# HV_Side.net
KiCad netlist of a schematic drawn in Altium Designer
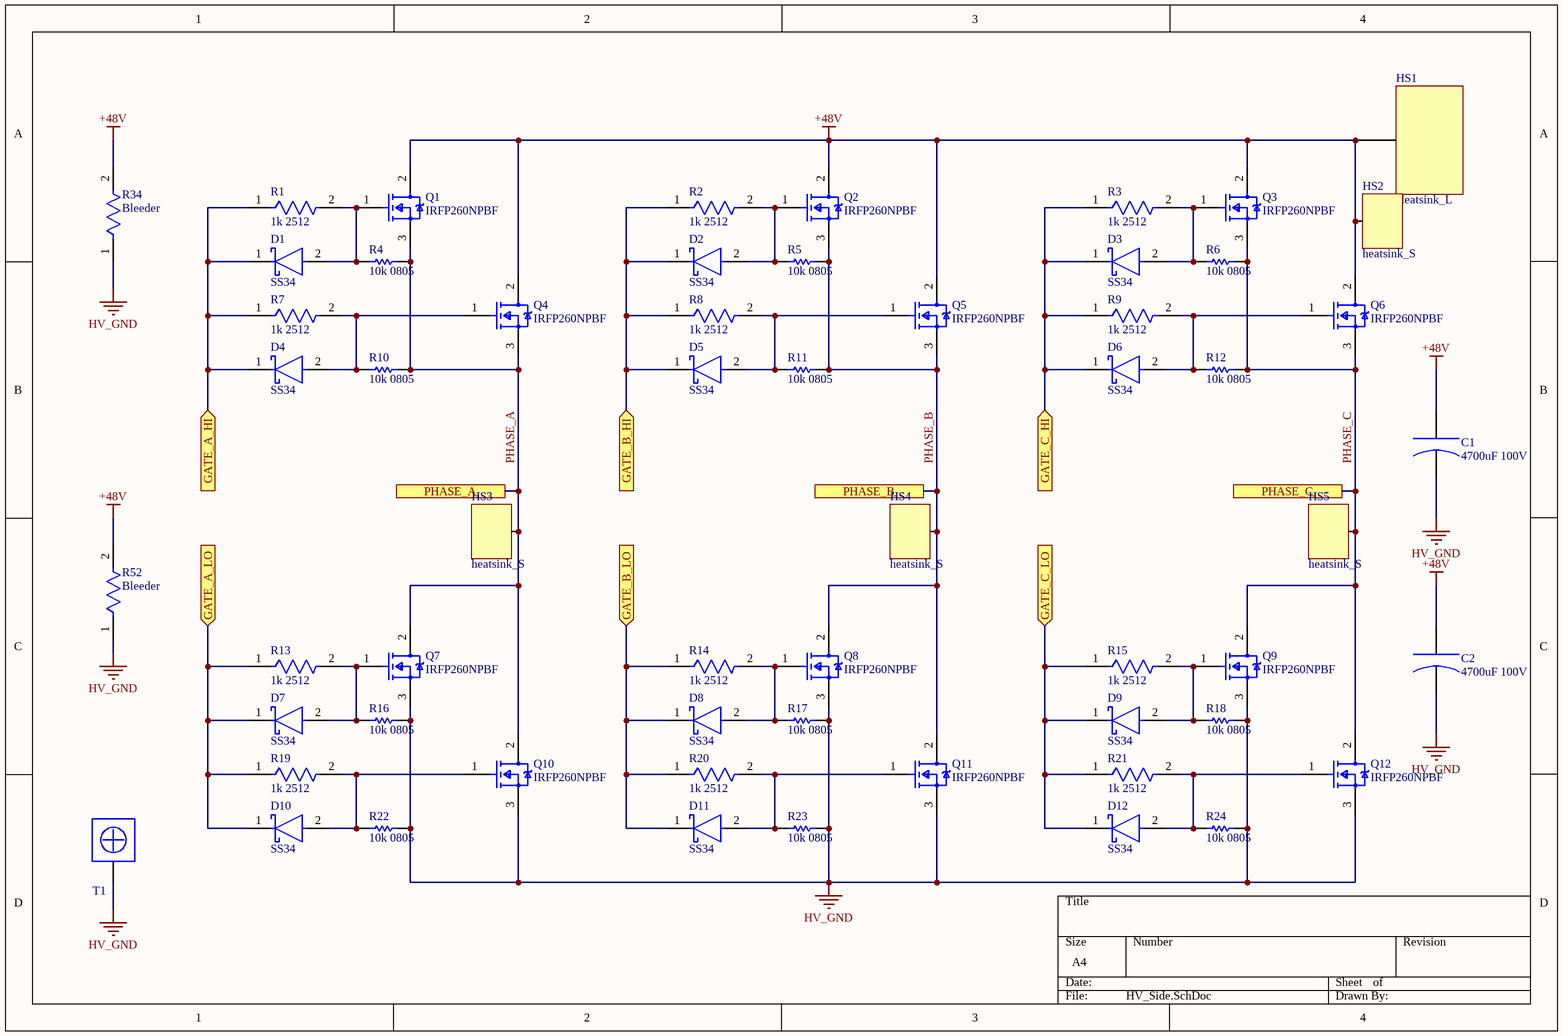
[diagram p0: HV_Side.SchDoc]

(export (version "E")
  (design (tool "Eeschema 10.0.6"))
  (components
    (comp (ref "C1")
      (value "4700uF 100V")
      (footprint "4700uF 100V")
      (description "4700uF 100V Electrolytic Capacitor")
      (libsource (lib "1kW_BLDC_Controller") (part "4700uF 100V"))
    )
    (comp (ref "C2")
      (value "4700uF 100V")
      (footprint "4700uF 100V")
      (description "4700uF 100V Electrolytic Capacitor")
      (libsource (lib "1kW_BLDC_Controller") (part "4700uF 100V"))
    )
    (comp (ref "D1")
      (value "SS34")
      (footprint "DO-214AC")
      (description "SS34 SMA 40V/3A Schottky Diode SMD Package-DO-214AC")
      (fields
        (field (name "MANUFACTURER") "Vishay Semiconductors")
        (field (name "MANUFACTURER PART NUMBER") "SS34-E3/57T")
      )
      (libsource (lib "1kW_BLDC_Controller") (part "SS34"))
    )
    (comp (ref "D2")
      (value "SS34")
      (footprint "DO-214AC")
      (description "SS34 SMA 40V/3A Schottky Diode SMD Package-DO-214AC")
      (fields
        (field (name "MANUFACTURER") "Vishay Semiconductors")
        (field (name "MANUFACTURER PART NUMBER") "SS34-E3/57T")
      )
      (libsource (lib "1kW_BLDC_Controller") (part "SS34"))
    )
    (comp (ref "D3")
      (value "SS34")
      (footprint "DO-214AC")
      (description "SS34 SMA 40V/3A Schottky Diode SMD Package-DO-214AC")
      (fields
        (field (name "MANUFACTURER") "Vishay Semiconductors")
        (field (name "MANUFACTURER PART NUMBER") "SS34-E3/57T")
      )
      (libsource (lib "1kW_BLDC_Controller") (part "SS34"))
    )
    (comp (ref "D4")
      (value "SS34")
      (footprint "DO-214AC")
      (description "SS34 SMA 40V/3A Schottky Diode SMD Package-DO-214AC")
      (fields
        (field (name "MANUFACTURER") "Vishay Semiconductors")
        (field (name "MANUFACTURER PART NUMBER") "SS34-E3/57T")
      )
      (libsource (lib "1kW_BLDC_Controller") (part "SS34"))
    )
    (comp (ref "D5")
      (value "SS34")
      (footprint "DO-214AC")
      (description "SS34 SMA 40V/3A Schottky Diode SMD Package-DO-214AC")
      (fields
        (field (name "MANUFACTURER") "Vishay Semiconductors")
        (field (name "MANUFACTURER PART NUMBER") "SS34-E3/57T")
      )
      (libsource (lib "1kW_BLDC_Controller") (part "SS34"))
    )
    (comp (ref "D6")
      (value "SS34")
      (footprint "DO-214AC")
      (description "SS34 SMA 40V/3A Schottky Diode SMD Package-DO-214AC")
      (fields
        (field (name "MANUFACTURER") "Vishay Semiconductors")
        (field (name "MANUFACTURER PART NUMBER") "SS34-E3/57T")
      )
      (libsource (lib "1kW_BLDC_Controller") (part "SS34"))
    )
    (comp (ref "D7")
      (value "SS34")
      (footprint "DO-214AC")
      (description "SS34 SMA 40V/3A Schottky Diode SMD Package-DO-214AC")
      (fields
        (field (name "MANUFACTURER") "Vishay Semiconductors")
        (field (name "MANUFACTURER PART NUMBER") "SS34-E3/57T")
      )
      (libsource (lib "1kW_BLDC_Controller") (part "SS34"))
    )
    (comp (ref "D8")
      (value "SS34")
      (footprint "DO-214AC")
      (description "SS34 SMA 40V/3A Schottky Diode SMD Package-DO-214AC")
      (fields
        (field (name "MANUFACTURER") "Vishay Semiconductors")
        (field (name "MANUFACTURER PART NUMBER") "SS34-E3/57T")
      )
      (libsource (lib "1kW_BLDC_Controller") (part "SS34"))
    )
    (comp (ref "D9")
      (value "SS34")
      (footprint "DO-214AC")
      (description "SS34 SMA 40V/3A Schottky Diode SMD Package-DO-214AC")
      (fields
        (field (name "MANUFACTURER") "Vishay Semiconductors")
        (field (name "MANUFACTURER PART NUMBER") "SS34-E3/57T")
      )
      (libsource (lib "1kW_BLDC_Controller") (part "SS34"))
    )
    (comp (ref "D10")
      (value "SS34")
      (footprint "DO-214AC")
      (description "SS34 SMA 40V/3A Schottky Diode SMD Package-DO-214AC")
      (fields
        (field (name "MANUFACTURER") "Vishay Semiconductors")
        (field (name "MANUFACTURER PART NUMBER") "SS34-E3/57T")
      )
      (libsource (lib "1kW_BLDC_Controller") (part "SS34"))
    )
    (comp (ref "D11")
      (value "SS34")
      (footprint "DO-214AC")
      (description "SS34 SMA 40V/3A Schottky Diode SMD Package-DO-214AC")
      (fields
        (field (name "MANUFACTURER") "Vishay Semiconductors")
        (field (name "MANUFACTURER PART NUMBER") "SS34-E3/57T")
      )
      (libsource (lib "1kW_BLDC_Controller") (part "SS34"))
    )
    (comp (ref "D12")
      (value "SS34")
      (footprint "DO-214AC")
      (description "SS34 SMA 40V/3A Schottky Diode SMD Package-DO-214AC")
      (fields
        (field (name "MANUFACTURER") "Vishay Semiconductors")
        (field (name "MANUFACTURER PART NUMBER") "SS34-E3/57T")
      )
      (libsource (lib "1kW_BLDC_Controller") (part "SS34"))
    )
    (comp (ref "HS1")
      (value "Heatsink_L")
      (footprint "heatsink_l")
      (libsource (lib "1kW_BLDC_Controller") (part "Heatsink_L"))
    )
    (comp (ref "HS2")
      (value "heatsink_S")
      (footprint "haetsink_s")
      (libsource (lib "") (part "heatsink_S_1"))
    )
    (comp (ref "HS3")
      (value "heatsink_S")
      (footprint "haetsink_s")
      (libsource (lib "1kW_BLDC_Controller") (part "heatsink_S"))
    )
    (comp (ref "HS4")
      (value "heatsink_S")
      (footprint "haetsink_s")
      (libsource (lib "1kW_BLDC_Controller") (part "heatsink_S"))
    )
    (comp (ref "HS5")
      (value "heatsink_S")
      (footprint "haetsink_s")
      (libsource (lib "1kW_BLDC_Controller") (part "heatsink_S"))
    )
    (comp (ref "Q1")
      (value "IRFP260NPBF")
      (footprint "FP-PG-TO247-3-MFG")
      (description "MOSFET N-CH 200V 50A TO247AC")
      (libsource (lib "Altium Content Vault") (part "b09f7f152735e370c1ea22a33fa83d6"))
    )
    (comp (ref "Q2")
      (value "IRFP260NPBF")
      (footprint "FP-PG-TO247-3-MFG")
      (description "MOSFET N-CH 200V 50A TO247AC")
      (libsource (lib "Altium Content Vault") (part "b09f7f152735e370c1ea22a33fa83d6"))
    )
    (comp (ref "Q3")
      (value "IRFP260NPBF")
      (footprint "FP-PG-TO247-3-MFG")
      (description "MOSFET N-CH 200V 50A TO247AC")
      (libsource (lib "Altium Content Vault") (part "b09f7f152735e370c1ea22a33fa83d6"))
    )
    (comp (ref "Q4")
      (value "IRFP260NPBF")
      (footprint "FP-PG-TO247-3-MFG")
      (description "MOSFET N-CH 200V 50A TO247AC")
      (libsource (lib "Altium Content Vault") (part "b09f7f152735e370c1ea22a33fa83d6"))
    )
    (comp (ref "Q5")
      (value "IRFP260NPBF")
      (footprint "FP-PG-TO247-3-MFG")
      (description "MOSFET N-CH 200V 50A TO247AC")
      (libsource (lib "Altium Content Vault") (part "b09f7f152735e370c1ea22a33fa83d6"))
    )
    (comp (ref "Q6")
      (value "IRFP260NPBF")
      (footprint "FP-PG-TO247-3-MFG")
      (description "MOSFET N-CH 200V 50A TO247AC")
      (libsource (lib "Altium Content Vault") (part "b09f7f152735e370c1ea22a33fa83d6"))
    )
    (comp (ref "Q7")
      (value "IRFP260NPBF")
      (footprint "FP-PG-TO247-3-MFG")
      (description "MOSFET N-CH 200V 50A TO247AC")
      (libsource (lib "Altium Content Vault") (part "b09f7f152735e370c1ea22a33fa83d6"))
    )
    (comp (ref "Q8")
      (value "IRFP260NPBF")
      (footprint "FP-PG-TO247-3-MFG")
      (description "MOSFET N-CH 200V 50A TO247AC")
      (libsource (lib "Altium Content Vault") (part "b09f7f152735e370c1ea22a33fa83d6"))
    )
    (comp (ref "Q9")
      (value "IRFP260NPBF")
      (footprint "FP-PG-TO247-3-MFG")
      (description "MOSFET N-CH 200V 50A TO247AC")
      (libsource (lib "Altium Content Vault") (part "b09f7f152735e370c1ea22a33fa83d6"))
    )
    (comp (ref "Q10")
      (value "IRFP260NPBF")
      (footprint "FP-PG-TO247-3-MFG")
      (description "MOSFET N-CH 200V 50A TO247AC")
      (libsource (lib "Altium Content Vault") (part "b09f7f152735e370c1ea22a33fa83d6"))
    )
    (comp (ref "Q11")
      (value "IRFP260NPBF")
      (footprint "FP-PG-TO247-3-MFG")
      (description "MOSFET N-CH 200V 50A TO247AC")
      (libsource (lib "Altium Content Vault") (part "b09f7f152735e370c1ea22a33fa83d6"))
    )
    (comp (ref "Q12")
      (value "IRFP260NPBF")
      (footprint "FP-PG-TO247-3-MFG")
      (description "MOSFET N-CH 200V 50A TO247AC")
      (libsource (lib "Altium Content Vault") (part "b09f7f152735e370c1ea22a33fa83d6"))
    )
    (comp (ref "R1")
      (value "1k 2512")
      (footprint "R2512")
      (description "1K Ohm 1W Resistor 2512 Package")
      (fields (field (name "TOLERANCE") "1%") (field (name "MANUFACTURER") "Vishay Dale"))
      (libsource (lib "1kW_BLDC_Controller") (part "1K_2512"))
    )
    (comp (ref "R2")
      (value "1k 2512")
      (footprint "R2512")
      (description "1K Ohm 1W Resistor 2512 Package")
      (fields (field (name "TOLERANCE") "1%") (field (name "MANUFACTURER") "Vishay Dale"))
      (libsource (lib "1kW_BLDC_Controller") (part "1K_2512"))
    )
    (comp (ref "R3")
      (value "1k 2512")
      (footprint "R2512")
      (description "1K Ohm 1W Resistor 2512 Package")
      (fields (field (name "TOLERANCE") "1%") (field (name "MANUFACTURER") "Vishay Dale"))
      (libsource (lib "1kW_BLDC_Controller") (part "1K_2512"))
    )
    (comp (ref "R4")
      (value "10k 0805")
      (footprint "R0805")
      (description "10K Ohm 1/8 Watt Resistor 1% Tolerance RC0805FR-0710KL – 0805 Package")
      (libsource (lib "1kW_BLDC_Controller") (part "10k 0805"))
    )
    (comp (ref "R5")
      (value "10k 0805")
      (footprint "R0805")
      (description "10K Ohm 1/8 Watt Resistor 1% Tolerance RC0805FR-0710KL – 0805 Package")
      (libsource (lib "1kW_BLDC_Controller") (part "10k 0805"))
    )
    (comp (ref "R6")
      (value "10k 0805")
      (footprint "R0805")
      (description "10K Ohm 1/8 Watt Resistor 1% Tolerance RC0805FR-0710KL – 0805 Package")
      (libsource (lib "1kW_BLDC_Controller") (part "10k 0805"))
    )
    (comp (ref "R7")
      (value "1k 2512")
      (footprint "R2512")
      (description "1K Ohm 1W Resistor 2512 Package")
      (fields (field (name "TOLERANCE") "1%") (field (name "MANUFACTURER") "Vishay Dale"))
      (libsource (lib "1kW_BLDC_Controller") (part "1K_2512"))
    )
    (comp (ref "R8")
      (value "1k 2512")
      (footprint "R2512")
      (description "1K Ohm 1W Resistor 2512 Package")
      (fields (field (name "TOLERANCE") "1%") (field (name "MANUFACTURER") "Vishay Dale"))
      (libsource (lib "1kW_BLDC_Controller") (part "1K_2512"))
    )
    (comp (ref "R9")
      (value "1k 2512")
      (footprint "R2512")
      (description "1K Ohm 1W Resistor 2512 Package")
      (fields (field (name "TOLERANCE") "1%") (field (name "MANUFACTURER") "Vishay Dale"))
      (libsource (lib "1kW_BLDC_Controller") (part "1K_2512"))
    )
    (comp (ref "R10")
      (value "10k 0805")
      (footprint "R0805")
      (description "10K Ohm 1/8 Watt Resistor 1% Tolerance RC0805FR-0710KL – 0805 Package")
      (libsource (lib "1kW_BLDC_Controller") (part "10k 0805"))
    )
    (comp (ref "R11")
      (value "10k 0805")
      (footprint "R0805")
      (description "10K Ohm 1/8 Watt Resistor 1% Tolerance RC0805FR-0710KL – 0805 Package")
      (libsource (lib "1kW_BLDC_Controller") (part "10k 0805"))
    )
    (comp (ref "R12")
      (value "10k 0805")
      (footprint "R0805")
      (description "10K Ohm 1/8 Watt Resistor 1% Tolerance RC0805FR-0710KL – 0805 Package")
      (libsource (lib "1kW_BLDC_Controller") (part "10k 0805"))
    )
    (comp (ref "R13")
      (value "1k 2512")
      (footprint "R2512")
      (description "1K Ohm 1W Resistor 2512 Package")
      (fields (field (name "TOLERANCE") "1%") (field (name "MANUFACTURER") "Vishay Dale"))
      (libsource (lib "1kW_BLDC_Controller") (part "1K_2512"))
    )
    (comp (ref "R14")
      (value "1k 2512")
      (footprint "R2512")
      (description "1K Ohm 1W Resistor 2512 Package")
      (fields (field (name "TOLERANCE") "1%") (field (name "MANUFACTURER") "Vishay Dale"))
      (libsource (lib "1kW_BLDC_Controller") (part "1K_2512"))
    )
    (comp (ref "R15")
      (value "1k 2512")
      (footprint "R2512")
      (description "1K Ohm 1W Resistor 2512 Package")
      (fields (field (name "TOLERANCE") "1%") (field (name "MANUFACTURER") "Vishay Dale"))
      (libsource (lib "1kW_BLDC_Controller") (part "1K_2512"))
    )
    (comp (ref "R16")
      (value "10k 0805")
      (footprint "R0805")
      (description "10K Ohm 1/8 Watt Resistor 1% Tolerance RC0805FR-0710KL – 0805 Package")
      (libsource (lib "1kW_BLDC_Controller") (part "10k 0805"))
    )
    (comp (ref "R17")
      (value "10k 0805")
      (footprint "R0805")
      (description "10K Ohm 1/8 Watt Resistor 1% Tolerance RC0805FR-0710KL – 0805 Package")
      (libsource (lib "1kW_BLDC_Controller") (part "10k 0805"))
    )
    (comp (ref "R18")
      (value "10k 0805")
      (footprint "R0805")
      (description "10K Ohm 1/8 Watt Resistor 1% Tolerance RC0805FR-0710KL – 0805 Package")
      (libsource (lib "1kW_BLDC_Controller") (part "10k 0805"))
    )
    (comp (ref "R19")
      (value "1k 2512")
      (footprint "R2512")
      (description "1K Ohm 1W Resistor 2512 Package")
      (fields (field (name "TOLERANCE") "1%") (field (name "MANUFACTURER") "Vishay Dale"))
      (libsource (lib "1kW_BLDC_Controller") (part "1K_2512"))
    )
    (comp (ref "R20")
      (value "1k 2512")
      (footprint "R2512")
      (description "1K Ohm 1W Resistor 2512 Package")
      (fields (field (name "TOLERANCE") "1%") (field (name "MANUFACTURER") "Vishay Dale"))
      (libsource (lib "1kW_BLDC_Controller") (part "1K_2512"))
    )
    (comp (ref "R21")
      (value "1k 2512")
      (footprint "R2512")
      (description "1K Ohm 1W Resistor 2512 Package")
      (fields (field (name "TOLERANCE") "1%") (field (name "MANUFACTURER") "Vishay Dale"))
      (libsource (lib "1kW_BLDC_Controller") (part "1K_2512"))
    )
    (comp (ref "R22")
      (value "10k 0805")
      (footprint "R0805")
      (description "10K Ohm 1/8 Watt Resistor 1% Tolerance RC0805FR-0710KL – 0805 Package")
      (libsource (lib "1kW_BLDC_Controller") (part "10k 0805"))
    )
    (comp (ref "R23")
      (value "10k 0805")
      (footprint "R0805")
      (description "10K Ohm 1/8 Watt Resistor 1% Tolerance RC0805FR-0710KL – 0805 Package")
      (libsource (lib "1kW_BLDC_Controller") (part "10k 0805"))
    )
    (comp (ref "R24")
      (value "10k 0805")
      (footprint "R0805")
      (description "10K Ohm 1/8 Watt Resistor 1% Tolerance RC0805FR-0710KL – 0805 Package")
      (libsource (lib "1kW_BLDC_Controller") (part "10k 0805"))
    )
    (comp (ref "R34")
      (value "Bleeder")
      (footprint "1W Modified THT")
      (libsource (lib "1kW_BLDC_Controller") (part "1W Bleeder"))
    )
    (comp (ref "R52")
      (value "Bleeder")
      (footprint "1W Modified THT")
      (libsource (lib "1kW_BLDC_Controller") (part "1W Bleeder"))
    )
    (comp (ref "T1")
      (value "7701 Keystone Terminal")
      (footprint "7701 Terminal")
      (libsource (lib "1kW_BLDC_Controller") (part "7701 Keystone Terminal"))
    )
  )
  (nets
    (net (code "1") (name "+48V") (class "Default")
      (node (ref "C1") (pin "1") (pinfunction "+_1") (pintype "power_in"))
      (node (ref "C2") (pin "1") (pinfunction "+_1") (pintype "power_in"))
      (node (ref "HS1") (pin "1") (pinfunction "1_1") (pintype "passive"))
      (node (ref "HS2") (pin "1") (pinfunction "1_1") (pintype "passive"))
      (node (ref "Q1") (pin "2") (pinfunction "D_2") (pintype "passive"))
      (node (ref "Q2") (pin "2") (pinfunction "D_2") (pintype "passive"))
      (node (ref "Q3") (pin "2") (pinfunction "D_2") (pintype "passive"))
      (node (ref "Q4") (pin "2") (pinfunction "D_2") (pintype "passive"))
      (node (ref "Q5") (pin "2") (pinfunction "D_2") (pintype "passive"))
      (node (ref "Q6") (pin "2") (pinfunction "D_2") (pintype "passive"))
      (node (ref "R34") (pin "2") (pinfunction "2_2") (pintype "passive"))
      (node (ref "R52") (pin "2") (pinfunction "2_2") (pintype "passive"))
    )
    (net (code "2") (name "/GATE_A_HI") (class "Default")
      (node (ref "D1") (pin "1") (pinfunction "C_1") (pintype "passive"))
      (node (ref "D4") (pin "1") (pinfunction "C_1") (pintype "passive"))
      (node (ref "R1") (pin "1") (pinfunction "1_1") (pintype "passive"))
      (node (ref "R7") (pin "1") (pinfunction "1_1") (pintype "passive"))
    )
    (net (code "3") (name "/GATE_A_LO") (class "Default")
      (node (ref "D10") (pin "1") (pinfunction "C_1") (pintype "passive"))
      (node (ref "D7") (pin "1") (pinfunction "C_1") (pintype "passive"))
      (node (ref "R13") (pin "1") (pinfunction "1_1") (pintype "passive"))
      (node (ref "R19") (pin "1") (pinfunction "1_1") (pintype "passive"))
    )
    (net (code "4") (name "/GATE_B_HI") (class "Default")
      (node (ref "D2") (pin "1") (pinfunction "C_1") (pintype "passive"))
      (node (ref "D5") (pin "1") (pinfunction "C_1") (pintype "passive"))
      (node (ref "R2") (pin "1") (pinfunction "1_1") (pintype "passive"))
      (node (ref "R8") (pin "1") (pinfunction "1_1") (pintype "passive"))
    )
    (net (code "5") (name "/GATE_B_LO") (class "Default")
      (node (ref "D11") (pin "1") (pinfunction "C_1") (pintype "passive"))
      (node (ref "D8") (pin "1") (pinfunction "C_1") (pintype "passive"))
      (node (ref "R14") (pin "1") (pinfunction "1_1") (pintype "passive"))
      (node (ref "R20") (pin "1") (pinfunction "1_1") (pintype "passive"))
    )
    (net (code "6") (name "/GATE_C_HI") (class "Default")
      (node (ref "D3") (pin "1") (pinfunction "C_1") (pintype "passive"))
      (node (ref "D6") (pin "1") (pinfunction "C_1") (pintype "passive"))
      (node (ref "R3") (pin "1") (pinfunction "1_1") (pintype "passive"))
      (node (ref "R9") (pin "1") (pinfunction "1_1") (pintype "passive"))
    )
    (net (code "7") (name "/GATE_C_LO") (class "Default")
      (node (ref "D12") (pin "1") (pinfunction "C_1") (pintype "passive"))
      (node (ref "D9") (pin "1") (pinfunction "C_1") (pintype "passive"))
      (node (ref "R15") (pin "1") (pinfunction "1_1") (pintype "passive"))
      (node (ref "R21") (pin "1") (pinfunction "1_1") (pintype "passive"))
    )
    (net (code "8") (name "/PHASE_A") (class "Default")
      (node (ref "HS3") (pin "1") (pinfunction "1_1") (pintype "passive"))
      (node (ref "Q1") (pin "3") (pinfunction "S_3") (pintype "passive"))
      (node (ref "Q10") (pin "2") (pinfunction "D_2") (pintype "passive"))
      (node (ref "Q4") (pin "3") (pinfunction "S_3") (pintype "passive"))
      (node (ref "Q7") (pin "2") (pinfunction "D_2") (pintype "passive"))
      (node (ref "R10") (pin "2") (pinfunction "2_2") (pintype "passive"))
      (node (ref "R4") (pin "2") (pinfunction "2_2") (pintype "passive"))
    )
    (net (code "9") (name "/PHASE_B") (class "Default")
      (node (ref "HS4") (pin "1") (pinfunction "1_1") (pintype "passive"))
      (node (ref "Q11") (pin "2") (pinfunction "D_2") (pintype "passive"))
      (node (ref "Q2") (pin "3") (pinfunction "S_3") (pintype "passive"))
      (node (ref "Q5") (pin "3") (pinfunction "S_3") (pintype "passive"))
      (node (ref "Q8") (pin "2") (pinfunction "D_2") (pintype "passive"))
      (node (ref "R11") (pin "2") (pinfunction "2_2") (pintype "passive"))
      (node (ref "R5") (pin "2") (pinfunction "2_2") (pintype "passive"))
    )
    (net (code "10") (name "/PHASE_C") (class "Default")
      (node (ref "HS5") (pin "1") (pinfunction "1_1") (pintype "passive"))
      (node (ref "Q12") (pin "2") (pinfunction "D_2") (pintype "passive"))
      (node (ref "Q3") (pin "3") (pinfunction "S_3") (pintype "passive"))
      (node (ref "Q6") (pin "3") (pinfunction "S_3") (pintype "passive"))
      (node (ref "Q9") (pin "2") (pinfunction "D_2") (pintype "passive"))
      (node (ref "R12") (pin "2") (pinfunction "2_2") (pintype "passive"))
      (node (ref "R6") (pin "2") (pinfunction "2_2") (pintype "passive"))
    )
    (net (code "11") (name "HV_GND") (class "Default")
      (node (ref "C1") (pin "2") (pinfunction "GND_2") (pintype "power_in"))
      (node (ref "C2") (pin "2") (pinfunction "GND_2") (pintype "power_in"))
      (node (ref "Q10") (pin "3") (pinfunction "S_3") (pintype "passive"))
      (node (ref "Q11") (pin "3") (pinfunction "S_3") (pintype "passive"))
      (node (ref "Q12") (pin "3") (pinfunction "S_3") (pintype "passive"))
      (node (ref "Q7") (pin "3") (pinfunction "S_3") (pintype "passive"))
      (node (ref "Q8") (pin "3") (pinfunction "S_3") (pintype "passive"))
      (node (ref "Q9") (pin "3") (pinfunction "S_3") (pintype "passive"))
      (node (ref "R16") (pin "2") (pinfunction "2_2") (pintype "passive"))
      (node (ref "R17") (pin "2") (pinfunction "2_2") (pintype "passive"))
      (node (ref "R18") (pin "2") (pinfunction "2_2") (pintype "passive"))
      (node (ref "R22") (pin "2") (pinfunction "2_2") (pintype "passive"))
      (node (ref "R23") (pin "2") (pinfunction "2_2") (pintype "passive"))
      (node (ref "R24") (pin "2") (pinfunction "2_2") (pintype "passive"))
      (node (ref "R34") (pin "1") (pinfunction "1_1") (pintype "passive"))
      (node (ref "R52") (pin "1") (pinfunction "1_1") (pintype "passive"))
      (node (ref "T1") (pin "1") (pinfunction "1_1") (pintype "passive"))
    )
    (net (code "12") (name "Net-(D1-A)") (class "Default")
      (node (ref "D1") (pin "2") (pinfunction "A_2") (pintype "passive"))
      (node (ref "Q1") (pin "1") (pinfunction "G_1") (pintype "passive"))
      (node (ref "R1") (pin "2") (pinfunction "2_2") (pintype "passive"))
      (node (ref "R4") (pin "1") (pinfunction "1_1") (pintype "passive"))
    )
    (net (code "13") (name "Net-(D2-A)") (class "Default")
      (node (ref "D2") (pin "2") (pinfunction "A_2") (pintype "passive"))
      (node (ref "Q2") (pin "1") (pinfunction "G_1") (pintype "passive"))
      (node (ref "R2") (pin "2") (pinfunction "2_2") (pintype "passive"))
      (node (ref "R5") (pin "1") (pinfunction "1_1") (pintype "passive"))
    )
    (net (code "14") (name "Net-(D3-A)") (class "Default")
      (node (ref "D3") (pin "2") (pinfunction "A_2") (pintype "passive"))
      (node (ref "Q3") (pin "1") (pinfunction "G_1") (pintype "passive"))
      (node (ref "R3") (pin "2") (pinfunction "2_2") (pintype "passive"))
      (node (ref "R6") (pin "1") (pinfunction "1_1") (pintype "passive"))
    )
    (net (code "15") (name "Net-(D4-A)") (class "Default")
      (node (ref "D4") (pin "2") (pinfunction "A_2") (pintype "passive"))
      (node (ref "Q4") (pin "1") (pinfunction "G_1") (pintype "passive"))
      (node (ref "R10") (pin "1") (pinfunction "1_1") (pintype "passive"))
      (node (ref "R7") (pin "2") (pinfunction "2_2") (pintype "passive"))
    )
    (net (code "16") (name "Net-(D5-A)") (class "Default")
      (node (ref "D5") (pin "2") (pinfunction "A_2") (pintype "passive"))
      (node (ref "Q5") (pin "1") (pinfunction "G_1") (pintype "passive"))
      (node (ref "R11") (pin "1") (pinfunction "1_1") (pintype "passive"))
      (node (ref "R8") (pin "2") (pinfunction "2_2") (pintype "passive"))
    )
    (net (code "17") (name "Net-(D6-A)") (class "Default")
      (node (ref "D6") (pin "2") (pinfunction "A_2") (pintype "passive"))
      (node (ref "Q6") (pin "1") (pinfunction "G_1") (pintype "passive"))
      (node (ref "R12") (pin "1") (pinfunction "1_1") (pintype "passive"))
      (node (ref "R9") (pin "2") (pinfunction "2_2") (pintype "passive"))
    )
    (net (code "18") (name "Net-(D7-A)") (class "Default")
      (node (ref "D7") (pin "2") (pinfunction "A_2") (pintype "passive"))
      (node (ref "Q7") (pin "1") (pinfunction "G_1") (pintype "passive"))
      (node (ref "R13") (pin "2") (pinfunction "2_2") (pintype "passive"))
      (node (ref "R16") (pin "1") (pinfunction "1_1") (pintype "passive"))
    )
    (net (code "19") (name "Net-(D8-A)") (class "Default")
      (node (ref "D8") (pin "2") (pinfunction "A_2") (pintype "passive"))
      (node (ref "Q8") (pin "1") (pinfunction "G_1") (pintype "passive"))
      (node (ref "R14") (pin "2") (pinfunction "2_2") (pintype "passive"))
      (node (ref "R17") (pin "1") (pinfunction "1_1") (pintype "passive"))
    )
    (net (code "20") (name "Net-(D9-A)") (class "Default")
      (node (ref "D9") (pin "2") (pinfunction "A_2") (pintype "passive"))
      (node (ref "Q9") (pin "1") (pinfunction "G_1") (pintype "passive"))
      (node (ref "R15") (pin "2") (pinfunction "2_2") (pintype "passive"))
      (node (ref "R18") (pin "1") (pinfunction "1_1") (pintype "passive"))
    )
    (net (code "21") (name "Net-(D10-A)") (class "Default")
      (node (ref "D10") (pin "2") (pinfunction "A_2") (pintype "passive"))
      (node (ref "Q10") (pin "1") (pinfunction "G_1") (pintype "passive"))
      (node (ref "R19") (pin "2") (pinfunction "2_2") (pintype "passive"))
      (node (ref "R22") (pin "1") (pinfunction "1_1") (pintype "passive"))
    )
    (net (code "22") (name "Net-(D11-A)") (class "Default")
      (node (ref "D11") (pin "2") (pinfunction "A_2") (pintype "passive"))
      (node (ref "Q11") (pin "1") (pinfunction "G_1") (pintype "passive"))
      (node (ref "R20") (pin "2") (pinfunction "2_2") (pintype "passive"))
      (node (ref "R23") (pin "1") (pinfunction "1_1") (pintype "passive"))
    )
    (net (code "23") (name "Net-(D12-A)") (class "Default")
      (node (ref "D12") (pin "2") (pinfunction "A_2") (pintype "passive"))
      (node (ref "Q12") (pin "1") (pinfunction "G_1") (pintype "passive"))
      (node (ref "R21") (pin "2") (pinfunction "2_2") (pintype "passive"))
      (node (ref "R24") (pin "1") (pinfunction "1_1") (pintype "passive"))
    )
  )
)
